# led_buttons.net
KiCad netlist of a schematic drawn in EAGLE
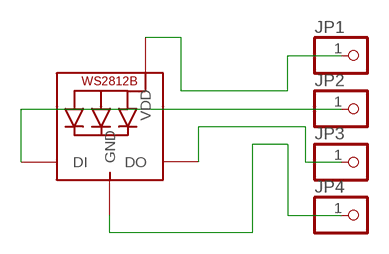
[diagram p0: schematic, sheet 1]

(export (version "E")
  (design (tool "Eeschema 10.0.6"))
  (components
    (comp (ref "JP1")
      (value "PINHD-1X1")
      (footprint "eagle-import:1X01")
      (libsource (lib "eagle-import") (part "PINHD-1X1"))
    )
    (comp (ref "JP2")
      (value "PINHD-1X1")
      (footprint "eagle-import:1X01")
      (libsource (lib "eagle-import") (part "PINHD-1X1"))
    )
    (comp (ref "JP3")
      (value "PINHD-1X1")
      (footprint "eagle-import:1X01")
      (libsource (lib "eagle-import") (part "PINHD-1X1"))
    )
    (comp (ref "JP4")
      (value "PINHD-1X1")
      (footprint "eagle-import:1X01")
      (libsource (lib "eagle-import") (part "PINHD-1X1"))
    )
    (comp (ref "LED1")
      (value "WS2812B5050")
      (footprint "eagle-import:WS2812B")
      (libsource (lib "eagle-import") (part "WS2812B5050"))
    )
  )
  (nets
    (net (code "1") (name "Net-(LED1-DI)") (class "Default")
      (node (ref "JP2") (pin "1") (pinfunction "1_1") (pintype "passive"))
      (node (ref "LED1") (pin "4-DIN") (pinfunction "DI_4-DIN") (pintype "input"))
    )
    (net (code "2") (name "Net-(LED1-DO)") (class "Default")
      (node (ref "JP3") (pin "1") (pinfunction "1_1") (pintype "passive"))
      (node (ref "LED1") (pin "2-DOUT") (pinfunction "DO_2-DOUT") (pintype "output"))
    )
    (net (code "3") (name "Net-(LED1-GND)") (class "Default")
      (node (ref "JP4") (pin "1") (pinfunction "1_1") (pintype "passive"))
      (node (ref "LED1") (pin "3-GND") (pinfunction "GND_3-GND") (pintype "power_in"))
    )
    (net (code "4") (name "Net-(LED1-VDD)") (class "Default")
      (node (ref "JP1") (pin "1") (pinfunction "1_1") (pintype "passive"))
      (node (ref "LED1") (pin "1-VDD") (pinfunction "VDD_1-VDD") (pintype "power_in"))
    )
  )
)
